# passive_attenumixer.net
KiCad netlist of a schematic drawn in EAGLE
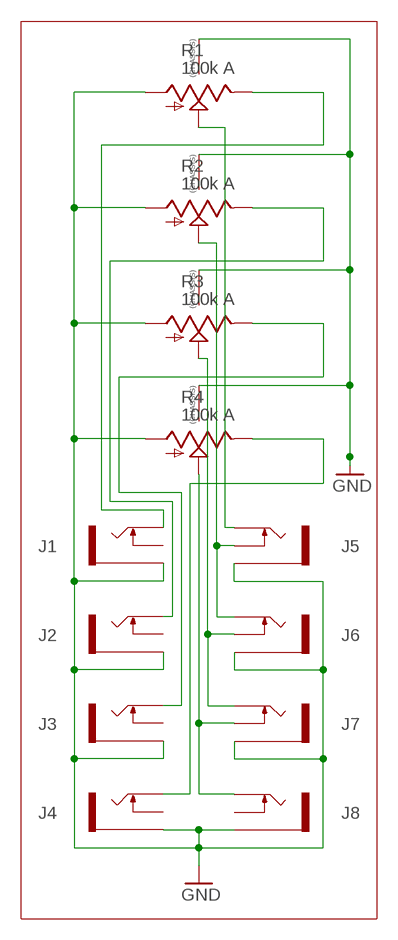
[diagram p0: schematic, sheet 1]

(export (version "E")
  (design (tool "Eeschema 10.0.6"))
  (components
    (comp (ref "J1")
      (value "THONKICONNNEW")
      (footprint "eagle-import:WQP-PJ301M-12_JACK")
      (libsource (lib "eagle-import") (part "THONKICONNNEW"))
    )
    (comp (ref "J2")
      (value "THONKICONNNEW")
      (footprint "eagle-import:WQP-PJ301M-12_JACK")
      (libsource (lib "eagle-import") (part "THONKICONNNEW"))
    )
    (comp (ref "J3")
      (value "THONKICONNNEW")
      (footprint "eagle-import:WQP-PJ301M-12_JACK")
      (libsource (lib "eagle-import") (part "THONKICONNNEW"))
    )
    (comp (ref "J4")
      (value "THONKICONNNEW")
      (footprint "eagle-import:WQP-PJ301M-12_JACK")
      (libsource (lib "eagle-import") (part "THONKICONNNEW"))
    )
    (comp (ref "J5")
      (value "THONKICONNNEW")
      (footprint "eagle-import:WQP-PJ301M-12_JACK")
      (libsource (lib "eagle-import") (part "THONKICONNNEW"))
    )
    (comp (ref "J6")
      (value "THONKICONNNEW")
      (footprint "eagle-import:WQP-PJ301M-12_JACK")
      (libsource (lib "eagle-import") (part "THONKICONNNEW"))
    )
    (comp (ref "J7")
      (value "THONKICONNNEW")
      (footprint "eagle-import:WQP-PJ301M-12_JACK")
      (libsource (lib "eagle-import") (part "THONKICONNNEW"))
    )
    (comp (ref "J8")
      (value "THONKICONNNEW")
      (footprint "eagle-import:WQP-PJ301M-12_JACK")
      (libsource (lib "eagle-import") (part "THONKICONNNEW"))
    )
    (comp (ref "R1")
      (value "100k A")
      (footprint "eagle-import:9MM_SNAP-IN_POT")
      (libsource (lib "eagle-import") (part "9MM_SNAP-IN_POT_CHASSIS"))
    )
    (comp (ref "R2")
      (value "100k A")
      (footprint "eagle-import:9MM_SNAP-IN_POT")
      (libsource (lib "eagle-import") (part "9MM_SNAP-IN_POT_CHASSIS"))
    )
    (comp (ref "R3")
      (value "100k A")
      (footprint "eagle-import:9MM_SNAP-IN_POT")
      (libsource (lib "eagle-import") (part "9MM_SNAP-IN_POT_CHASSIS"))
    )
    (comp (ref "R4")
      (value "100k A")
      (footprint "eagle-import:9MM_SNAP-IN_POT")
      (libsource (lib "eagle-import") (part "9MM_SNAP-IN_POT_CHASSIS"))
    )
  )
  (nets
    (net (code "1") (name "GND") (class "Default")
      (node (ref "J1") (pin "P$3_SLEEVE") (pinfunction "SLEEVE_P$3_SLEEVE") (pintype "passive"))
      (node (ref "J2") (pin "P$3_SLEEVE") (pinfunction "SLEEVE_P$3_SLEEVE") (pintype "passive"))
      (node (ref "J3") (pin "P$3_SLEEVE") (pinfunction "SLEEVE_P$3_SLEEVE") (pintype "passive"))
      (node (ref "J4") (pin "P$3_SLEEVE") (pinfunction "SLEEVE_P$3_SLEEVE") (pintype "passive"))
      (node (ref "J5") (pin "P$3_SLEEVE") (pinfunction "SLEEVE_P$3_SLEEVE") (pintype "passive"))
      (node (ref "J6") (pin "P$3_SLEEVE") (pinfunction "SLEEVE_P$3_SLEEVE") (pintype "passive"))
      (node (ref "J7") (pin "P$3_SLEEVE") (pinfunction "SLEEVE_P$3_SLEEVE") (pintype "passive"))
      (node (ref "J8") (pin "P$3_SLEEVE") (pinfunction "SLEEVE_P$3_SLEEVE") (pintype "passive"))
      (node (ref "R1") (pin "1") (pinfunction "A_1") (pintype "passive"))
      (node (ref "R1") (pin "CHASSIS1") (pinfunction "P$1_CHASSIS1") (pintype "passive"))
      (node (ref "R1") (pin "CHASSIS2") (pinfunction "P$1_CHASSIS2") (pintype "passive"))
      (node (ref "R2") (pin "1") (pinfunction "A_1") (pintype "passive"))
      (node (ref "R2") (pin "CHASSIS1") (pinfunction "P$1_CHASSIS1") (pintype "passive"))
      (node (ref "R2") (pin "CHASSIS2") (pinfunction "P$1_CHASSIS2") (pintype "passive"))
      (node (ref "R3") (pin "1") (pinfunction "A_1") (pintype "passive"))
      (node (ref "R3") (pin "CHASSIS1") (pinfunction "P$1_CHASSIS1") (pintype "passive"))
      (node (ref "R3") (pin "CHASSIS2") (pinfunction "P$1_CHASSIS2") (pintype "passive"))
      (node (ref "R4") (pin "1") (pinfunction "A_1") (pintype "passive"))
      (node (ref "R4") (pin "CHASSIS1") (pinfunction "P$1_CHASSIS1") (pintype "passive"))
      (node (ref "R4") (pin "CHASSIS2") (pinfunction "P$1_CHASSIS2") (pintype "passive"))
    )
    (net (code "2") (name "Net-(J1-TIP)") (class "Default")
      (node (ref "J1") (pin "P$1_TIP") (pinfunction "TIP_P$1_TIP") (pintype "passive"))
      (node (ref "R1") (pin "3") (pinfunction "E_3") (pintype "passive"))
    )
    (net (code "3") (name "Net-(J2-TIP)") (class "Default")
      (node (ref "J2") (pin "P$1_TIP") (pinfunction "TIP_P$1_TIP") (pintype "passive"))
      (node (ref "R2") (pin "3") (pinfunction "E_3") (pintype "passive"))
    )
    (net (code "4") (name "Net-(J3-TIP)") (class "Default")
      (node (ref "J3") (pin "P$1_TIP") (pinfunction "TIP_P$1_TIP") (pintype "passive"))
      (node (ref "R3") (pin "3") (pinfunction "E_3") (pintype "passive"))
    )
    (net (code "5") (name "Net-(J4-TIP)") (class "Default")
      (node (ref "J4") (pin "P$1_TIP") (pinfunction "TIP_P$1_TIP") (pintype "passive"))
      (node (ref "R4") (pin "3") (pinfunction "E_3") (pintype "passive"))
    )
    (net (code "6") (name "Net-(J5-SWITCH)") (class "Default")
      (node (ref "J5") (pin "P$2_SWITCH") (pinfunction "SWITCH_P$2_SWITCH") (pintype "passive"))
      (node (ref "J6") (pin "P$1_TIP") (pinfunction "TIP_P$1_TIP") (pintype "passive"))
      (node (ref "R2") (pin "2") (pinfunction "S_2") (pintype "passive"))
    )
    (net (code "7") (name "Net-(J5-TIP)") (class "Default")
      (node (ref "J5") (pin "P$1_TIP") (pinfunction "TIP_P$1_TIP") (pintype "passive"))
      (node (ref "R1") (pin "2") (pinfunction "S_2") (pintype "passive"))
    )
    (net (code "8") (name "Net-(J6-SWITCH)") (class "Default")
      (node (ref "J6") (pin "P$2_SWITCH") (pinfunction "SWITCH_P$2_SWITCH") (pintype "passive"))
      (node (ref "J7") (pin "P$1_TIP") (pinfunction "TIP_P$1_TIP") (pintype "passive"))
      (node (ref "R3") (pin "2") (pinfunction "S_2") (pintype "passive"))
    )
    (net (code "9") (name "Net-(J7-SWITCH)") (class "Default")
      (node (ref "J7") (pin "P$2_SWITCH") (pinfunction "SWITCH_P$2_SWITCH") (pintype "passive"))
      (node (ref "J8") (pin "P$1_TIP") (pinfunction "TIP_P$1_TIP") (pintype "passive"))
      (node (ref "R4") (pin "2") (pinfunction "S_2") (pintype "passive"))
    )
    (net (code "10") (name "unconnected-(J1-SWITCH-PadP$2_SWITCH)") (class "Default")
      (node (ref "J1") (pin "P$2_SWITCH") (pinfunction "SWITCH_P$2_SWITCH") (pintype "passive"))
    )
    (net (code "11") (name "unconnected-(J2-SWITCH-PadP$2_SWITCH)") (class "Default")
      (node (ref "J2") (pin "P$2_SWITCH") (pinfunction "SWITCH_P$2_SWITCH") (pintype "passive"))
    )
    (net (code "12") (name "unconnected-(J3-SWITCH-PadP$2_SWITCH)") (class "Default")
      (node (ref "J3") (pin "P$2_SWITCH") (pinfunction "SWITCH_P$2_SWITCH") (pintype "passive"))
    )
    (net (code "13") (name "unconnected-(J4-SWITCH-PadP$2_SWITCH)") (class "Default")
      (node (ref "J4") (pin "P$2_SWITCH") (pinfunction "SWITCH_P$2_SWITCH") (pintype "passive"))
    )
    (net (code "14") (name "unconnected-(J8-SWITCH-PadP$2_SWITCH)") (class "Default")
      (node (ref "J8") (pin "P$2_SWITCH") (pinfunction "SWITCH_P$2_SWITCH") (pintype "passive"))
    )
  )
)
